# ESP32-S3.net
KiCad netlist of a schematic drawn in Altium Designer
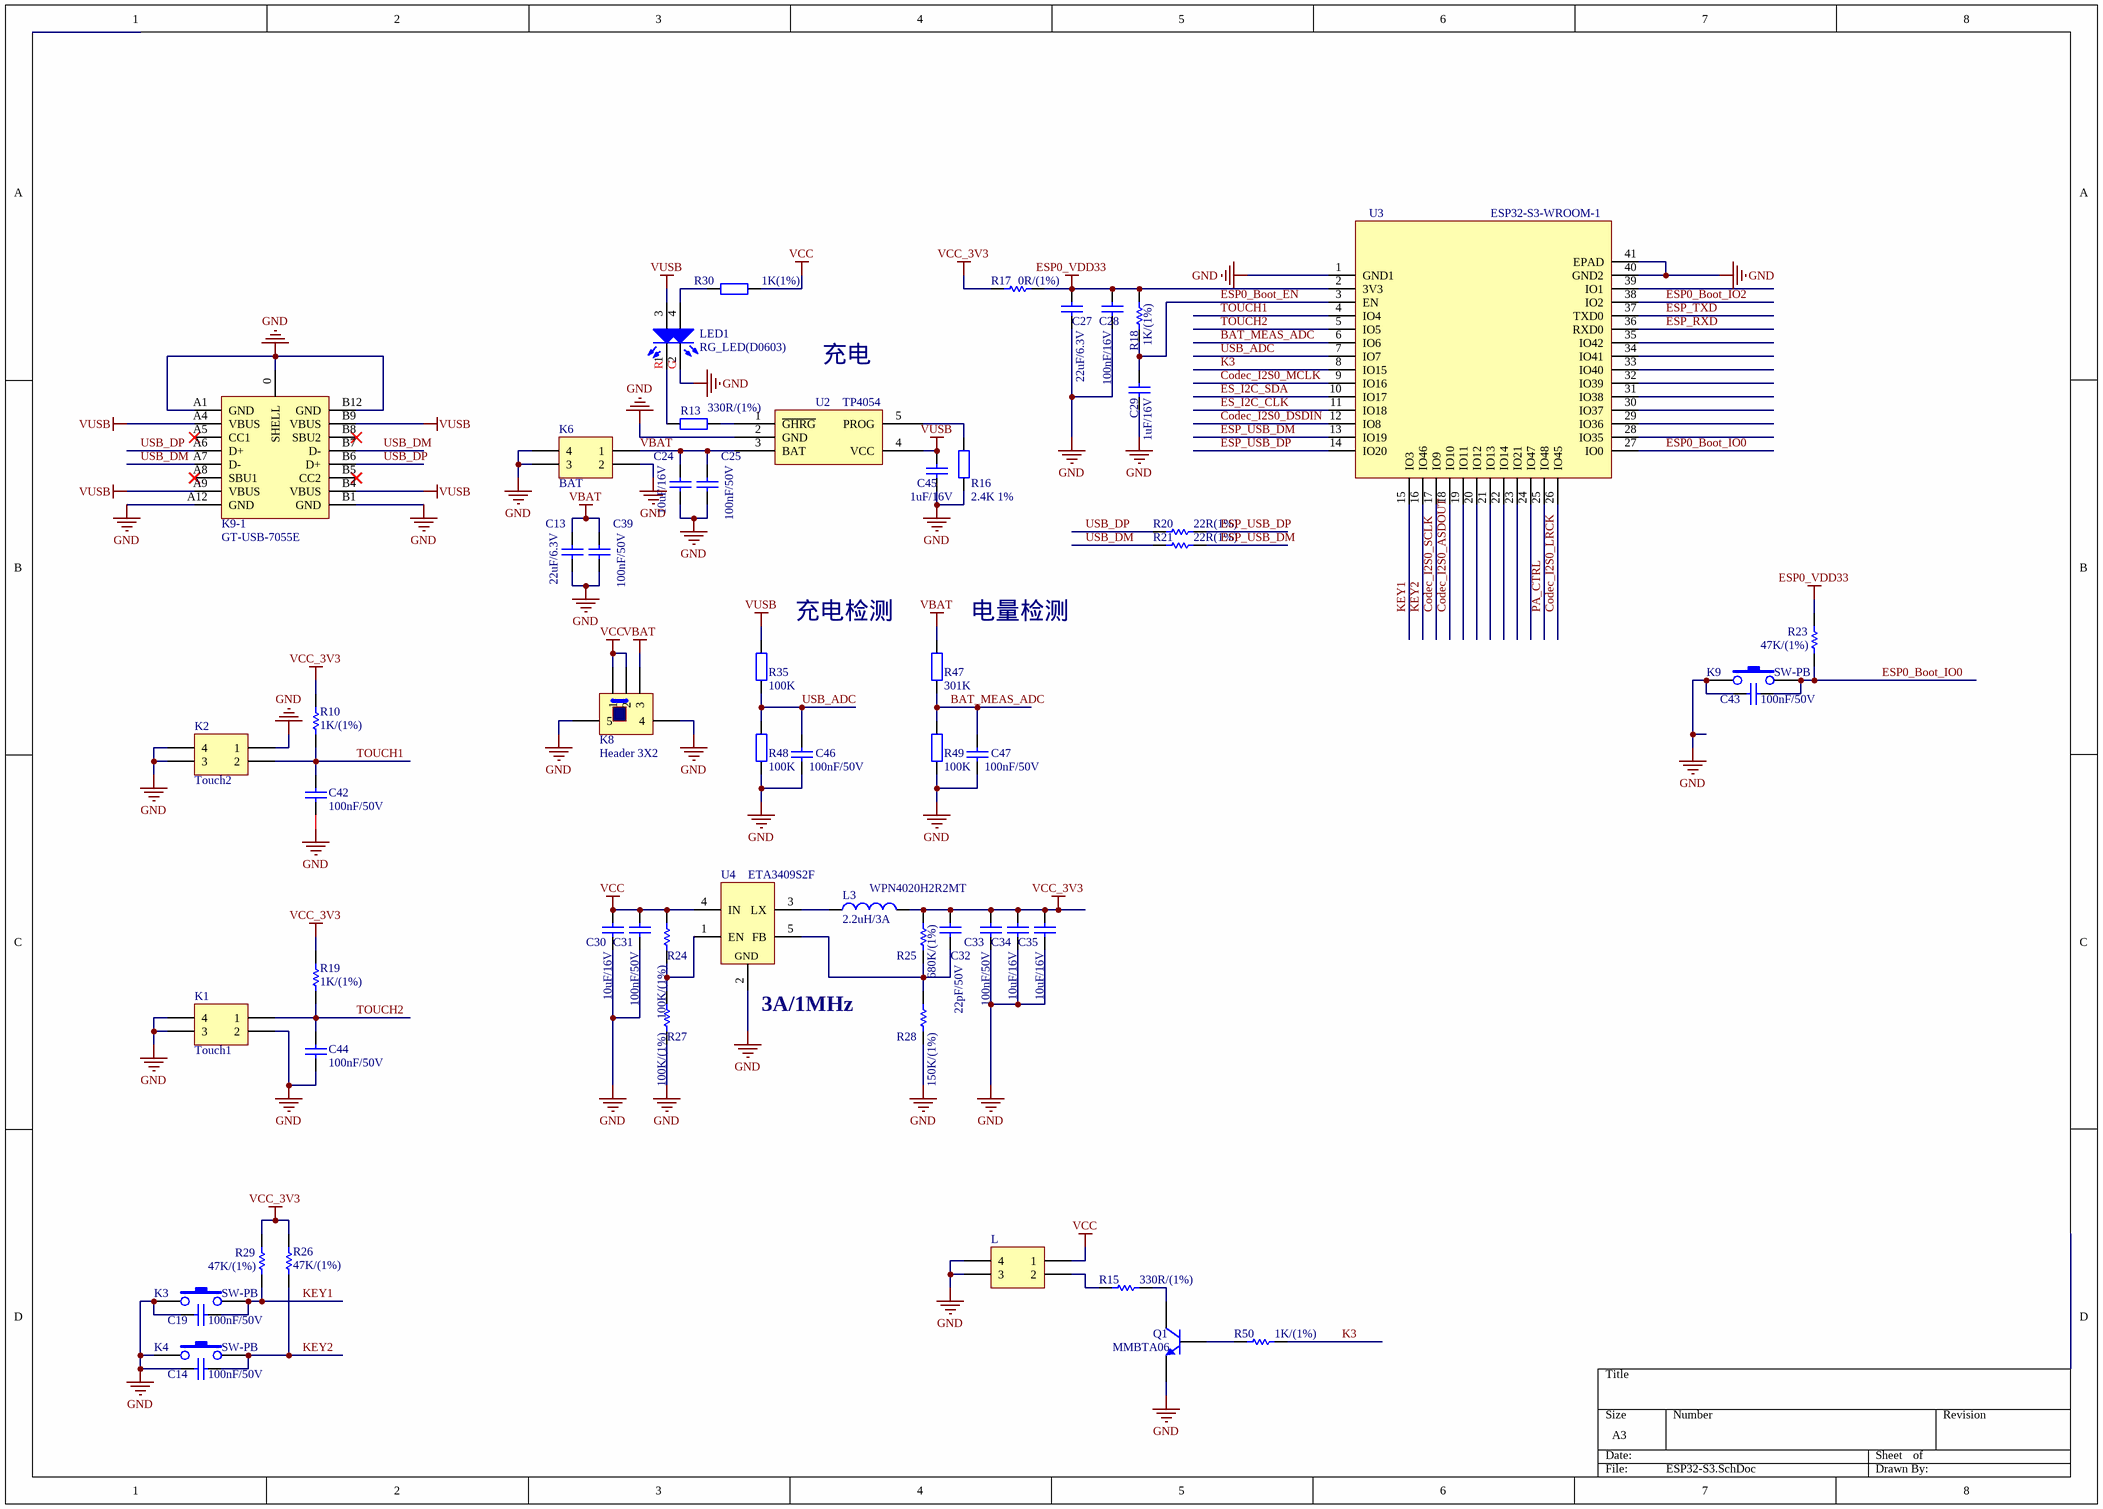
[diagram p0: ESP32-S3.SchDoc]

(export (version "E")
  (design (tool "Eeschema 10.0.6"))
  (components
    (comp (ref "C13")
      (value "22uF/6.3V")
      (footprint "C0402")
      (description "贴片电容")
      (libsource (lib "*") (part "0603 10uF (106) 10% 10V"))
    )
    (comp (ref "C14")
      (value "100nF/50V")
      (footprint "C0402")
      (description "Capacitor")
      (fields (field (name "PUBLISHER") "Altium Limited"))
      (libsource (lib "Miscellaneous Devices") (part "Cap"))
    )
    (comp (ref "C19")
      (value "100nF/50V")
      (footprint "C0402")
      (description "Capacitor")
      (fields (field (name "PUBLISHER") "Altium Limited"))
      (libsource (lib "Miscellaneous Devices") (part "Cap"))
    )
    (comp (ref "C24")
      (value "10uF/16V")
      (footprint "C0402")
      (description "贴片电容")
      (libsource (lib "*") (part "0603 10uF (106) 10% 10V"))
    )
    (comp (ref "C25")
      (value "100nF/50V")
      (footprint "C0402")
      (description "贴片电容")
      (libsource (lib "*") (part "0402 100nF (104) 10% 16V"))
    )
    (comp (ref "C27")
      (value "22uF/6.3V")
      (footprint "C0402")
      (description "Capacitor")
      (fields (field (name "PUBLISHER") "Altium Limited"))
      (libsource (lib "Miscellaneous Devices") (part "Cap"))
    )
    (comp (ref "C28")
      (value "100nF/16V")
      (footprint "C0402")
      (description "Capacitor")
      (fields (field (name "PUBLISHER") "Altium Limited"))
      (libsource (lib "Miscellaneous Devices") (part "Cap"))
    )
    (comp (ref "C29")
      (value "1uF/16V")
      (footprint "C0402")
      (description "Capacitor")
      (fields (field (name "PUBLISHER") "Altium Limited"))
      (libsource (lib "Miscellaneous Devices") (part "Cap"))
    )
    (comp (ref "C30")
      (value "10uF/16V")
      (footprint "C0402")
      (description "Capacitor")
      (fields (field (name "PUBLISHER") "Altium Limited"))
      (libsource (lib "Miscellaneous Devices") (part "Cap"))
    )
    (comp (ref "C31")
      (value "100nF/50V")
      (footprint "C0402")
      (description "Capacitor")
      (fields (field (name "PUBLISHER") "Altium Limited"))
      (libsource (lib "Miscellaneous Devices") (part "Cap"))
    )
    (comp (ref "C32")
      (value "22pF/50V")
      (footprint "C0402")
      (description "Capacitor")
      (fields (field (name "PUBLISHER") "Altium Limited"))
      (libsource (lib "Miscellaneous Devices") (part "Cap"))
    )
    (comp (ref "C33")
      (value "100nF/50V")
      (footprint "C0402")
      (description "Capacitor")
      (fields (field (name "PUBLISHER") "Altium Limited"))
      (libsource (lib "Miscellaneous Devices") (part "Cap"))
    )
    (comp (ref "C34")
      (value "10uF/16V")
      (footprint "C0402")
      (description "Capacitor")
      (fields (field (name "PUBLISHER") "Altium Limited"))
      (libsource (lib "Miscellaneous Devices") (part "Cap"))
    )
    (comp (ref "C35")
      (value "10uF/16V")
      (footprint "C0402")
      (description "Capacitor")
      (fields (field (name "PUBLISHER") "Altium Limited"))
      (libsource (lib "Miscellaneous Devices") (part "Cap"))
    )
    (comp (ref "C39")
      (value "100nF/50V")
      (footprint "C0402")
      (description "贴片电容")
      (libsource (lib "*") (part "0402 100nF (104) 10% 16V"))
    )
    (comp (ref "C42")
      (value "100nF/50V")
      (footprint "C0402")
      (description "Capacitor")
      (fields (field (name "PUBLISHER") "Altium Limited"))
      (libsource (lib "Miscellaneous Devices") (part "Cap"))
    )
    (comp (ref "C43")
      (value "100nF/50V")
      (footprint "C0402")
      (description "Capacitor")
      (fields (field (name "PUBLISHER") "Altium Limited"))
      (libsource (lib "Miscellaneous Devices") (part "Cap"))
    )
    (comp (ref "C44")
      (value "100nF/50V")
      (footprint "C0402")
      (description "Capacitor")
      (fields (field (name "PUBLISHER") "Altium Limited"))
      (libsource (lib "Miscellaneous Devices") (part "Cap"))
    )
    (comp (ref "C45")
      (value "1uF/16V")
      (footprint "C0402")
      (description "贴片电容")
      (libsource (lib "*") (part "0603 470nF (474) 10% 25V"))
    )
    (comp (ref "C46")
      (value "100nF/50V")
      (footprint "C0402")
      (description "贴片电容")
      (libsource (lib "*") (part "0603 1.0pF (010) 0.25pF 50V"))
    )
    (comp (ref "C47")
      (value "100nF/50V")
      (footprint "C0402")
      (description "贴片电容")
      (libsource (lib "*") (part "0603 1.0pF (010) 0.25pF 50V"))
    )
    (comp (ref "K1")
      (value "Touch1")
      (footprint "HC-1.25-2PWT")
      (description "Header, 2-Pin, Dual row")
      (fields (field (name "PUBLISHER") "Altium Limited"))
      (libsource (lib "Miscellaneous Connectors") (part "Header 2X2"))
    )
    (comp (ref "K2")
      (value "Touch2")
      (footprint "HC-1.25-2PWT")
      (description "Header, 2-Pin, Dual row")
      (fields (field (name "PUBLISHER") "Altium Limited"))
      (libsource (lib "Miscellaneous Connectors") (part "Header 2X2"))
    )
    (comp (ref "K3") (value "SW-PB") (footprint "K(3*4*2.5H)") (libsource (lib "ESP32-S3") (part "SW-PB")))
    (comp (ref "K4") (value "SW-PB") (footprint "K(3*4*2.5H)") (libsource (lib "ESP32-S3") (part "SW-PB")))
    (comp (ref "K6")
      (value "BAT")
      (footprint "HC-1.25-2PWT")
      (description "Header, 2-Pin, Dual row")
      (fields (field (name "PUBLISHER") "Altium Limited"))
      (libsource (lib "Miscellaneous Connectors") (part "Header 2X2"))
    )
    (comp (ref "K8")
      (value "Header 3X2")
      (footprint "SS12D07VG4 087")
      (description "Header, 3-Pin, Dual row")
      (fields (field (name "PUBLISHER") "Altium Limited"))
      (libsource (lib "聊天机器人") (part "Header 3X2"))
    )
    (comp (ref "K9") (value "SW-PB") (footprint "K(3*4*2.5H)") (libsource (lib "ESP32-S3") (part "SW-PB")))
    (comp (ref "K9-1")
      (value "GT-USB-7055E")
      (footprint "GT-USB-7055E")
      (libsource (lib "聊天机器人") (part "GT-USB-7055E"))
    )
    (comp (ref "L")
      (value "~")
      (footprint "HC-1.25-2PWT")
      (description "Header, 2-Pin, Dual row")
      (fields (field (name "PUBLISHER") "Altium Limited"))
      (libsource (lib "Miscellaneous Connectors") (part "Header 2X2"))
    )
    (comp (ref "L3")
      (value "2.2uH/3A")
      (footprint "SWPA4020")
      (description "Inductor")
      (fields (field (name "PUBLISHER") "Altium Limited"))
      (libsource (lib "Miscellaneous Devices") (part "Inductor"))
    )
    (comp (ref "LED1")
      (value "RG_LED(D0603)")
      (footprint "LED-SMD_4P-L1.6")
      (libsource (lib "ESP32-S3") (part "RG_LED"))
    )
    (comp (ref "Q1")
      (value "MMBTA06")
      (footprint "SOT-23")
      (description "NPN General Purpose Amplifier")
      (fields (field (name "PUBLISHER") "Altium Limited"))
      (libsource (lib "Miscellaneous Devices") (part "2N3904"))
    )
    (comp (ref "R10")
      (value "1K/(1%)")
      (footprint "R0402")
      (description "Resistor")
      (fields (field (name "PUBLISHER") "Altium Limited"))
      (libsource (lib "Miscellaneous Devices") (part "Res1"))
    )
    (comp (ref "R13")
      (value "330R/(1%)")
      (footprint "R0402")
      (description "贴片电阻")
      (libsource (lib "*") (part "0402 1KΩ (1001) 1%"))
    )
    (comp (ref "R15")
      (value "330R/(1%)")
      (footprint "R0402")
      (description "Resistor")
      (fields (field (name "PUBLISHER") "Altium Limited"))
      (libsource (lib "Miscellaneous Devices") (part "Res1"))
    )
    (comp (ref "R16")
      (value "2.4K 1%")
      (footprint "R0402")
      (description "贴片电阻")
      (libsource (lib "*") (part "0402 2.4KΩ (2401) 1%"))
    )
    (comp (ref "R17")
      (value "0R/(1%)")
      (footprint "R0402")
      (description "Resistor")
      (fields (field (name "PUBLISHER") "Altium Limited"))
      (libsource (lib "Miscellaneous Devices") (part "Res1"))
    )
    (comp (ref "R18")
      (value "1K/(1%)")
      (footprint "R0402")
      (description "Resistor")
      (fields (field (name "PUBLISHER") "Altium Limited"))
      (libsource (lib "Miscellaneous Devices") (part "Res1"))
    )
    (comp (ref "R19")
      (value "1K/(1%)")
      (footprint "R0402")
      (description "Resistor")
      (fields (field (name "PUBLISHER") "Altium Limited"))
      (libsource (lib "Miscellaneous Devices") (part "Res1"))
    )
    (comp (ref "R20")
      (value "22R(1%)")
      (footprint "R0402")
      (description "Resistor")
      (fields (field (name "PUBLISHER") "Altium Limited"))
      (libsource (lib "Miscellaneous Devices") (part "Res1"))
    )
    (comp (ref "R21")
      (value "22R(1%)")
      (footprint "R0402")
      (description "Resistor")
      (fields (field (name "PUBLISHER") "Altium Limited"))
      (libsource (lib "Miscellaneous Devices") (part "Res1"))
    )
    (comp (ref "R23")
      (value "47K/(1%)")
      (footprint "R0402")
      (description "Resistor")
      (fields (field (name "PUBLISHER") "Altium Limited"))
      (libsource (lib "Miscellaneous Devices") (part "Res1"))
    )
    (comp (ref "R24")
      (value "100K/(1%)")
      (footprint "R0402")
      (description "Resistor")
      (fields (field (name "PUBLISHER") "Altium Limited"))
      (libsource (lib "Miscellaneous Devices") (part "Res1"))
    )
    (comp (ref "R25")
      (value "680K/(1%)")
      (footprint "R0402")
      (description "Resistor")
      (fields (field (name "PUBLISHER") "Altium Limited"))
      (libsource (lib "Miscellaneous Devices") (part "Res1"))
    )
    (comp (ref "R26")
      (value "47K/(1%)")
      (footprint "R0402")
      (description "Resistor")
      (fields (field (name "PUBLISHER") "Altium Limited"))
      (libsource (lib "Miscellaneous Devices") (part "Res1"))
    )
    (comp (ref "R27")
      (value "100K/(1%)")
      (footprint "R0402")
      (description "Resistor")
      (fields (field (name "PUBLISHER") "Altium Limited"))
      (libsource (lib "Miscellaneous Devices") (part "Res1"))
    )
    (comp (ref "R28")
      (value "150K/(1%)")
      (footprint "R0402")
      (description "Resistor")
      (fields (field (name "PUBLISHER") "Altium Limited"))
      (libsource (lib "Miscellaneous Devices") (part "Res1"))
    )
    (comp (ref "R29")
      (value "47K/(1%)")
      (footprint "R0402")
      (description "Resistor")
      (fields (field (name "PUBLISHER") "Altium Limited"))
      (libsource (lib "Miscellaneous Devices") (part "Res1"))
    )
    (comp (ref "R30")
      (value "1K(1%)")
      (footprint "R0402")
      (description "贴片电阻")
      (libsource (lib "*") (part "0402 1KΩ (1001) 1%"))
    )
    (comp (ref "R35")
      (value "100K")
      (footprint "R0402")
      (description "贴片电阻")
      (libsource (lib "*") (part "0402 100KΩ (1003) 1%"))
    )
    (comp (ref "R47")
      (value "301K")
      (footprint "R0402")
      (description "贴片电阻")
      (libsource (lib "*") (part "0402 100KΩ (1003) 1%"))
    )
    (comp (ref "R48")
      (value "100K")
      (footprint "R0402")
      (description "贴片电阻")
      (libsource (lib "*") (part "0402 100KΩ (1003) 1%"))
    )
    (comp (ref "R49")
      (value "100K")
      (footprint "R0402")
      (description "贴片电阻")
      (libsource (lib "*") (part "0402 100KΩ (1003) 1%"))
    )
    (comp (ref "R50")
      (value "1K/(1%)")
      (footprint "R0402")
      (description "Resistor")
      (fields (field (name "PUBLISHER") "Altium Limited"))
      (libsource (lib "Miscellaneous Devices") (part "Res1"))
    )
    (comp (ref "U2")
      (value "TP4054")
      (footprint "SOT-23-5")
      (description "电池电源管理")
      (libsource (lib "*") (part "TP4054"))
    )
    (comp (ref "U3")
      (value "ESP32-S3-WROOM-1")
      (footprint "ESP32-S3-WROOM-1")
      (libsource (lib "ESP32-S3") (part "ESP32-S3-WROOM-1"))
    )
    (comp (ref "U4")
      (value "ETA3409S2F")
      (footprint "SOT23-5_ETA3409S2F")
      (libsource (lib "ESP32-S3") (part "ETA3409S2F"))
    )
  )
  (nets
    (net (code "1") (name "/BAT_MEAS_ADC") (class "Default")
      (node (ref "C47") (pin "1") (pinfunction "1_1") (pintype "passive"))
      (node (ref "R47") (pin "1") (pinfunction "1_1") (pintype "passive"))
      (node (ref "R49") (pin "2") (pinfunction "2_2") (pintype "passive"))
      (node (ref "U3") (pin "6") (pinfunction "IO6_6") (pintype "passive"))
    )
    (net (code "2") (name "/Codec_I2S0_ASDOUT") (class "Default")
      (node (ref "U3") (pin "18") (pinfunction "IO10_18") (pintype "passive"))
    )
    (net (code "3") (name "/Codec_I2S0_DSDIN") (class "Default")
      (node (ref "U3") (pin "12") (pinfunction "IO8_12") (pintype "passive"))
    )
    (net (code "4") (name "/Codec_I2S0_LRCK") (class "Default")
      (node (ref "U3") (pin "26") (pinfunction "IO45_26") (pintype "passive"))
    )
    (net (code "5") (name "/Codec_I2S0_MCLK") (class "Default")
      (node (ref "U3") (pin "9") (pinfunction "IO16_9") (pintype "passive"))
    )
    (net (code "6") (name "/Codec_I2S0_SCLK") (class "Default")
      (node (ref "U3") (pin "17") (pinfunction "IO9_17") (pintype "passive"))
    )
    (net (code "7") (name "/ESP0_Boot_EN") (class "Default")
      (node (ref "C29") (pin "2") (pinfunction "2_2") (pintype "passive"))
      (node (ref "R18") (pin "2") (pinfunction "2_2") (pintype "passive"))
      (node (ref "U3") (pin "3") (pinfunction "EN_3") (pintype "passive"))
    )
    (net (code "8") (name "/ESP0_Boot_IO0") (class "Default")
      (node (ref "C43") (pin "1") (pinfunction "1_1") (pintype "passive"))
      (node (ref "K9") (pin "2") (pinfunction "2_2") (pintype "passive"))
      (node (ref "R23") (pin "2") (pinfunction "2_2") (pintype "passive"))
      (node (ref "U3") (pin "27") (pinfunction "IO0_27") (pintype "passive"))
    )
    (net (code "9") (name "/ESP0_Boot_IO2") (class "Default")
      (node (ref "U3") (pin "38") (pinfunction "IO2_38") (pintype "passive"))
    )
    (net (code "10") (name "/ESP_RXD") (class "Default")
      (node (ref "U3") (pin "36") (pinfunction "RXD0_36") (pintype "passive"))
    )
    (net (code "11") (name "/ESP_TXD") (class "Default")
      (node (ref "U3") (pin "37") (pinfunction "TXD0_37") (pintype "passive"))
    )
    (net (code "12") (name "/ESP_USB_DM") (class "Default")
      (node (ref "R21") (pin "1") (pinfunction "1_1") (pintype "passive"))
      (node (ref "U3") (pin "13") (pinfunction "IO19_13") (pintype "passive"))
    )
    (net (code "13") (name "/ESP_USB_DP") (class "Default")
      (node (ref "R20") (pin "1") (pinfunction "1_1") (pintype "passive"))
      (node (ref "U3") (pin "14") (pinfunction "IO20_14") (pintype "passive"))
    )
    (net (code "14") (name "/ES_I2C_CLK") (class "Default")
      (node (ref "U3") (pin "11") (pinfunction "IO18_11") (pintype "passive"))
    )
    (net (code "15") (name "/ES_I2C_SDA") (class "Default")
      (node (ref "U3") (pin "10") (pinfunction "IO17_10") (pintype "passive"))
    )
    (net (code "16") (name "/K3") (class "Default")
      (node (ref "R50") (pin "1") (pinfunction "1_1") (pintype "passive"))
      (node (ref "U3") (pin "8") (pinfunction "IO15_8") (pintype "passive"))
    )
    (net (code "17") (name "/KEY1") (class "Default")
      (node (ref "C19") (pin "1") (pinfunction "1_1") (pintype "passive"))
      (node (ref "K3") (pin "2") (pinfunction "2_2") (pintype "passive"))
      (node (ref "R29") (pin "2") (pinfunction "2_2") (pintype "passive"))
      (node (ref "U3") (pin "15") (pinfunction "IO3_15") (pintype "passive"))
    )
    (net (code "18") (name "/KEY2") (class "Default")
      (node (ref "C14") (pin "1") (pinfunction "1_1") (pintype "passive"))
      (node (ref "K4") (pin "1") (pinfunction "1_1") (pintype "passive"))
      (node (ref "R26") (pin "2") (pinfunction "2_2") (pintype "passive"))
      (node (ref "U3") (pin "16") (pinfunction "IO46_16") (pintype "passive"))
    )
    (net (code "19") (name "/PA_CTRL") (class "Default")
      (node (ref "U3") (pin "25") (pinfunction "IO48_25") (pintype "passive"))
    )
    (net (code "20") (name "/TOUCH1") (class "Default")
      (node (ref "C42") (pin "1") (pinfunction "1_1") (pintype "passive"))
      (node (ref "K2") (pin "2") (pinfunction "2_2") (pintype "passive"))
      (node (ref "R10") (pin "2") (pinfunction "2_2") (pintype "passive"))
      (node (ref "U3") (pin "4") (pinfunction "IO4_4") (pintype "passive"))
    )
    (net (code "21") (name "/TOUCH2") (class "Default")
      (node (ref "C44") (pin "1") (pinfunction "1_1") (pintype "passive"))
      (node (ref "K1") (pin "1") (pinfunction "1_1") (pintype "passive"))
      (node (ref "R19") (pin "2") (pinfunction "2_2") (pintype "passive"))
      (node (ref "U3") (pin "5") (pinfunction "IO5_5") (pintype "passive"))
    )
    (net (code "22") (name "/USB_ADC") (class "Default")
      (node (ref "C46") (pin "1") (pinfunction "1_1") (pintype "passive"))
      (node (ref "R35") (pin "1") (pinfunction "1_1") (pintype "passive"))
      (node (ref "R48") (pin "2") (pinfunction "2_2") (pintype "passive"))
      (node (ref "U3") (pin "7") (pinfunction "IO7_7") (pintype "passive"))
    )
    (net (code "23") (name "/USB_DM") (class "Default")
      (node (ref "K9-1") (pin "A7") (pinfunction "D-_A7") (pintype "passive"))
      (node (ref "K9-1") (pin "B7") (pinfunction "D-_B7") (pintype "passive"))
      (node (ref "R21") (pin "2") (pinfunction "2_2") (pintype "passive"))
    )
    (net (code "24") (name "/USB_DP") (class "Default")
      (node (ref "K9-1") (pin "A6") (pinfunction "D+_A6") (pintype "passive"))
      (node (ref "K9-1") (pin "B6") (pinfunction "D+_B6") (pintype "passive"))
      (node (ref "R20") (pin "2") (pinfunction "2_2") (pintype "passive"))
    )
    (net (code "25") (name "ESP0_VDD33") (class "Default")
      (node (ref "C27") (pin "2") (pinfunction "2_2") (pintype "passive"))
      (node (ref "C28") (pin "2") (pinfunction "2_2") (pintype "passive"))
      (node (ref "R17") (pin "2") (pinfunction "2_2") (pintype "passive"))
      (node (ref "R18") (pin "1") (pinfunction "1_1") (pintype "passive"))
      (node (ref "R23") (pin "1") (pinfunction "1_1") (pintype "passive"))
      (node (ref "U3") (pin "2") (pinfunction "3V3_2") (pintype "passive"))
    )
    (net (code "26") (name "GND") (class "Default")
      (node (ref "C13") (pin "1") (pinfunction "1_1") (pintype "passive"))
      (node (ref "C14") (pin "2") (pinfunction "2_2") (pintype "passive"))
      (node (ref "C19") (pin "2") (pinfunction "2_2") (pintype "passive"))
      (node (ref "C24") (pin "1") (pinfunction "1_1") (pintype "passive"))
      (node (ref "C25") (pin "1") (pinfunction "1_1") (pintype "passive"))
      (node (ref "C27") (pin "1") (pinfunction "1_1") (pintype "passive"))
      (node (ref "C28") (pin "1") (pinfunction "1_1") (pintype "passive"))
      (node (ref "C29") (pin "1") (pinfunction "1_1") (pintype "passive"))
      (node (ref "C30") (pin "1") (pinfunction "1_1") (pintype "passive"))
      (node (ref "C31") (pin "1") (pinfunction "1_1") (pintype "passive"))
      (node (ref "C33") (pin "1") (pinfunction "1_1") (pintype "passive"))
      (node (ref "C34") (pin "1") (pinfunction "1_1") (pintype "passive"))
      (node (ref "C35") (pin "1") (pinfunction "1_1") (pintype "passive"))
      (node (ref "C39") (pin "1") (pinfunction "1_1") (pintype "passive"))
      (node (ref "C42") (pin "2") (pinfunction "2_2") (pintype "passive"))
      (node (ref "C43") (pin "2") (pinfunction "2_2") (pintype "passive"))
      (node (ref "C44") (pin "2") (pinfunction "2_2") (pintype "passive"))
      (node (ref "C45") (pin "2") (pinfunction "2_2") (pintype "passive"))
      (node (ref "C46") (pin "2") (pinfunction "2_2") (pintype "passive"))
      (node (ref "C47") (pin "2") (pinfunction "2_2") (pintype "passive"))
      (node (ref "K1") (pin "2") (pinfunction "2_2") (pintype "passive"))
      (node (ref "K1") (pin "3") (pinfunction "3_3") (pintype "passive"))
      (node (ref "K1") (pin "4") (pinfunction "4_4") (pintype "passive"))
      (node (ref "K2") (pin "1") (pinfunction "1_1") (pintype "passive"))
      (node (ref "K2") (pin "3") (pinfunction "3_3") (pintype "passive"))
      (node (ref "K2") (pin "4") (pinfunction "4_4") (pintype "passive"))
      (node (ref "K3") (pin "1") (pinfunction "1_1") (pintype "passive"))
      (node (ref "K4") (pin "2") (pinfunction "2_2") (pintype "passive"))
      (node (ref "K6") (pin "2") (pinfunction "2_2") (pintype "passive"))
      (node (ref "K6") (pin "3") (pinfunction "3_3") (pintype "passive"))
      (node (ref "K6") (pin "4") (pinfunction "4_4") (pintype "passive"))
      (node (ref "K8") (pin "4") (pinfunction "4_4") (pintype "passive"))
      (node (ref "K8") (pin "5") (pinfunction "5_5") (pintype "passive"))
      (node (ref "K9") (pin "1") (pinfunction "1_1") (pintype "passive"))
      (node (ref "K9-1") (pin "0") (pinfunction "SHELL_0") (pintype "passive"))
      (node (ref "K9-1") (pin "A1") (pinfunction "GND_A1") (pintype "passive"))
      (node (ref "K9-1") (pin "A12") (pinfunction "GND_A12") (pintype "passive"))
      (node (ref "K9-1") (pin "B1") (pinfunction "GND_B1") (pintype "passive"))
      (node (ref "K9-1") (pin "B12") (pinfunction "GND_B12") (pintype "passive"))
      (node (ref "L") (pin "3") (pinfunction "3_3") (pintype "passive"))
      (node (ref "L") (pin "4") (pinfunction "4_4") (pintype "passive"))
      (node (ref "LED1") (pin "2") (pinfunction "2_2") (pintype "passive"))
      (node (ref "Q1") (pin "2") (pinfunction "E_2") (pintype "passive"))
      (node (ref "R16") (pin "1") (pinfunction "1_1") (pintype "passive"))
      (node (ref "R27") (pin "2") (pinfunction "2_2") (pintype "passive"))
      (node (ref "R28") (pin "2") (pinfunction "2_2") (pintype "passive"))
      (node (ref "R48") (pin "1") (pinfunction "1_1") (pintype "passive"))
      (node (ref "R49") (pin "1") (pinfunction "1_1") (pintype "passive"))
      (node (ref "U2") (pin "2") (pinfunction "GND_2") (pintype "passive"))
      (node (ref "U3") (pin "1") (pinfunction "GND1_1") (pintype "passive"))
      (node (ref "U3") (pin "40") (pinfunction "GND2_40") (pintype "passive"))
      (node (ref "U3") (pin "41") (pinfunction "EPAD_41") (pintype "passive"))
      (node (ref "U4") (pin "2") (pinfunction "GND_2") (pintype "passive"))
    )
    (net (code "27") (name "Net-(L-Pad2)") (class "Default")
      (node (ref "L") (pin "2") (pinfunction "2_2") (pintype "passive"))
      (node (ref "R15") (pin "2") (pinfunction "2_2") (pintype "passive"))
    )
    (net (code "28") (name "Net-(LED1-Pad1)") (class "Default")
      (node (ref "LED1") (pin "1") (pinfunction "1_1") (pintype "passive"))
      (node (ref "R13") (pin "1") (pinfunction "1_1") (pintype "passive"))
    )
    (net (code "29") (name "Net-(LED1-Pad4)") (class "Default")
      (node (ref "LED1") (pin "4") (pinfunction "4_4") (pintype "passive"))
      (node (ref "R30") (pin "1") (pinfunction "1_1") (pintype "passive"))
    )
    (net (code "30") (name "Net-(Q1-B)") (class "Default")
      (node (ref "Q1") (pin "1") (pinfunction "B_1") (pintype "passive"))
      (node (ref "R50") (pin "2") (pinfunction "2_2") (pintype "passive"))
    )
    (net (code "31") (name "Net-(Q1-C)") (class "Default")
      (node (ref "Q1") (pin "3") (pinfunction "C_3") (pintype "passive"))
      (node (ref "R15") (pin "1") (pinfunction "1_1") (pintype "passive"))
    )
    (net (code "32") (name "Net-(U2-PROG)") (class "Default")
      (node (ref "R16") (pin "2") (pinfunction "2_2") (pintype "passive"))
      (node (ref "U2") (pin "5") (pinfunction "PROG_5") (pintype "passive"))
    )
    (net (code "33") (name "Net-(U2-~{GHRG})") (class "Default")
      (node (ref "R13") (pin "2") (pinfunction "2_2") (pintype "passive"))
      (node (ref "U2") (pin "1") (pinfunction "~{GHRG}_1") (pintype "passive"))
    )
    (net (code "34") (name "Net-(U4-EN)") (class "Default")
      (node (ref "R24") (pin "2") (pinfunction "2_2") (pintype "passive"))
      (node (ref "R27") (pin "1") (pinfunction "1_1") (pintype "passive"))
      (node (ref "U4") (pin "1") (pinfunction "EN_1") (pintype "passive"))
    )
    (net (code "35") (name "Net-(U4-FB)") (class "Default")
      (node (ref "C32") (pin "1") (pinfunction "1_1") (pintype "passive"))
      (node (ref "R25") (pin "2") (pinfunction "2_2") (pintype "passive"))
      (node (ref "R28") (pin "1") (pinfunction "1_1") (pintype "passive"))
      (node (ref "U4") (pin "5") (pinfunction "FB_5") (pintype "passive"))
    )
    (net (code "36") (name "Net-(U4-LX)") (class "Default")
      (node (ref "L3") (pin "1") (pinfunction "1_1") (pintype "passive"))
      (node (ref "U4") (pin "3") (pinfunction "LX_3") (pintype "passive"))
    )
    (net (code "37") (name "VBAT") (class "Default")
      (node (ref "C13") (pin "2") (pinfunction "2_2") (pintype "passive"))
      (node (ref "C24") (pin "2") (pinfunction "2_2") (pintype "passive"))
      (node (ref "C25") (pin "2") (pinfunction "2_2") (pintype "passive"))
      (node (ref "C39") (pin "2") (pinfunction "2_2") (pintype "passive"))
      (node (ref "K6") (pin "1") (pinfunction "1_1") (pintype "passive"))
      (node (ref "K8") (pin "3") (pinfunction "3_3") (pintype "passive"))
      (node (ref "R47") (pin "2") (pinfunction "2_2") (pintype "passive"))
      (node (ref "U2") (pin "3") (pinfunction "BAT_3") (pintype "passive"))
    )
    (net (code "38") (name "VCC") (class "Default")
      (node (ref "C30") (pin "2") (pinfunction "2_2") (pintype "passive"))
      (node (ref "C31") (pin "2") (pinfunction "2_2") (pintype "passive"))
      (node (ref "K8") (pin "1") (pinfunction "1_1") (pintype "passive"))
      (node (ref "K8") (pin "2") (pinfunction "2_2") (pintype "passive"))
      (node (ref "L") (pin "1") (pinfunction "1_1") (pintype "passive"))
      (node (ref "R24") (pin "1") (pinfunction "1_1") (pintype "passive"))
      (node (ref "R30") (pin "2") (pinfunction "2_2") (pintype "passive"))
      (node (ref "U4") (pin "4") (pinfunction "IN_4") (pintype "passive"))
    )
    (net (code "39") (name "VCC_3V3") (class "Default")
      (node (ref "C32") (pin "2") (pinfunction "2_2") (pintype "passive"))
      (node (ref "C33") (pin "2") (pinfunction "2_2") (pintype "passive"))
      (node (ref "C34") (pin "2") (pinfunction "2_2") (pintype "passive"))
      (node (ref "C35") (pin "2") (pinfunction "2_2") (pintype "passive"))
      (node (ref "L3") (pin "2") (pinfunction "2_2") (pintype "passive"))
      (node (ref "R10") (pin "1") (pinfunction "1_1") (pintype "passive"))
      (node (ref "R17") (pin "1") (pinfunction "1_1") (pintype "passive"))
      (node (ref "R19") (pin "1") (pinfunction "1_1") (pintype "passive"))
      (node (ref "R25") (pin "1") (pinfunction "1_1") (pintype "passive"))
      (node (ref "R26") (pin "1") (pinfunction "1_1") (pintype "passive"))
      (node (ref "R29") (pin "1") (pinfunction "1_1") (pintype "passive"))
    )
    (net (code "40") (name "VUSB") (class "Default")
      (node (ref "C45") (pin "1") (pinfunction "1_1") (pintype "passive"))
      (node (ref "K9-1") (pin "A4") (pinfunction "VBUS_A4") (pintype "passive"))
      (node (ref "K9-1") (pin "A9") (pinfunction "VBUS_A9") (pintype "passive"))
      (node (ref "K9-1") (pin "B4") (pinfunction "VBUS_B4") (pintype "passive"))
      (node (ref "K9-1") (pin "B9") (pinfunction "VBUS_B9") (pintype "passive"))
      (node (ref "LED1") (pin "3") (pinfunction "3_3") (pintype "passive"))
      (node (ref "R35") (pin "2") (pinfunction "2_2") (pintype "passive"))
      (node (ref "U2") (pin "4") (pinfunction "VCC_4") (pintype "passive"))
    )
    (net (code "41") (name "unconnected-(K9-1-CC1-PadA5)") (class "Default")
      (node (ref "K9-1") (pin "A5") (pinfunction "CC1_A5") (pintype "passive+no_connect"))
    )
    (net (code "42") (name "unconnected-(K9-1-CC2-PadB5)") (class "Default")
      (node (ref "K9-1") (pin "B5") (pinfunction "CC2_B5") (pintype "passive+no_connect"))
    )
    (net (code "43") (name "unconnected-(K9-1-SBU1-PadA8)") (class "Default")
      (node (ref "K9-1") (pin "A8") (pinfunction "SBU1_A8") (pintype "passive+no_connect"))
    )
    (net (code "44") (name "unconnected-(K9-1-SBU2-PadB8)") (class "Default")
      (node (ref "K9-1") (pin "B8") (pinfunction "SBU2_B8") (pintype "passive+no_connect"))
    )
    (net (code "45") (name "unconnected-(U3-IO1-Pad39)") (class "Default")
      (node (ref "U3") (pin "39") (pinfunction "IO1_39") (pintype "passive"))
    )
    (net (code "46") (name "unconnected-(U3-IO11-Pad19)") (class "Default")
      (node (ref "U3") (pin "19") (pinfunction "IO11_19") (pintype "passive"))
    )
    (net (code "47") (name "unconnected-(U3-IO12-Pad20)") (class "Default")
      (node (ref "U3") (pin "20") (pinfunction "IO12_20") (pintype "passive"))
    )
    (net (code "48") (name "unconnected-(U3-IO13-Pad21)") (class "Default")
      (node (ref "U3") (pin "21") (pinfunction "IO13_21") (pintype "passive"))
    )
    (net (code "49") (name "unconnected-(U3-IO14-Pad22)") (class "Default")
      (node (ref "U3") (pin "22") (pinfunction "IO14_22") (pintype "passive"))
    )
    (net (code "50") (name "unconnected-(U3-IO21-Pad23)") (class "Default")
      (node (ref "U3") (pin "23") (pinfunction "IO21_23") (pintype "passive"))
    )
    (net (code "51") (name "unconnected-(U3-IO35-Pad28)") (class "Default")
      (node (ref "U3") (pin "28") (pinfunction "IO35_28") (pintype "passive"))
    )
    (net (code "52") (name "unconnected-(U3-IO36-Pad29)") (class "Default")
      (node (ref "U3") (pin "29") (pinfunction "IO36_29") (pintype "passive"))
    )
    (net (code "53") (name "unconnected-(U3-IO37-Pad30)") (class "Default")
      (node (ref "U3") (pin "30") (pinfunction "IO37_30") (pintype "passive"))
    )
    (net (code "54") (name "unconnected-(U3-IO38-Pad31)") (class "Default")
      (node (ref "U3") (pin "31") (pinfunction "IO38_31") (pintype "passive"))
    )
    (net (code "55") (name "unconnected-(U3-IO39-Pad32)") (class "Default")
      (node (ref "U3") (pin "32") (pinfunction "IO39_32") (pintype "passive"))
    )
    (net (code "56") (name "unconnected-(U3-IO40-Pad33)") (class "Default")
      (node (ref "U3") (pin "33") (pinfunction "IO40_33") (pintype "passive"))
    )
    (net (code "57") (name "unconnected-(U3-IO41-Pad34)") (class "Default")
      (node (ref "U3") (pin "34") (pinfunction "IO41_34") (pintype "passive"))
    )
    (net (code "58") (name "unconnected-(U3-IO42-Pad35)") (class "Default")
      (node (ref "U3") (pin "35") (pinfunction "IO42_35") (pintype "passive"))
    )
    (net (code "59") (name "unconnected-(U3-IO47-Pad24)") (class "Default")
      (node (ref "U3") (pin "24") (pinfunction "IO47_24") (pintype "passive"))
    )
  )
)
